# NEW_oct_6.net
KiCad netlist of a schematic drawn in EAGLE
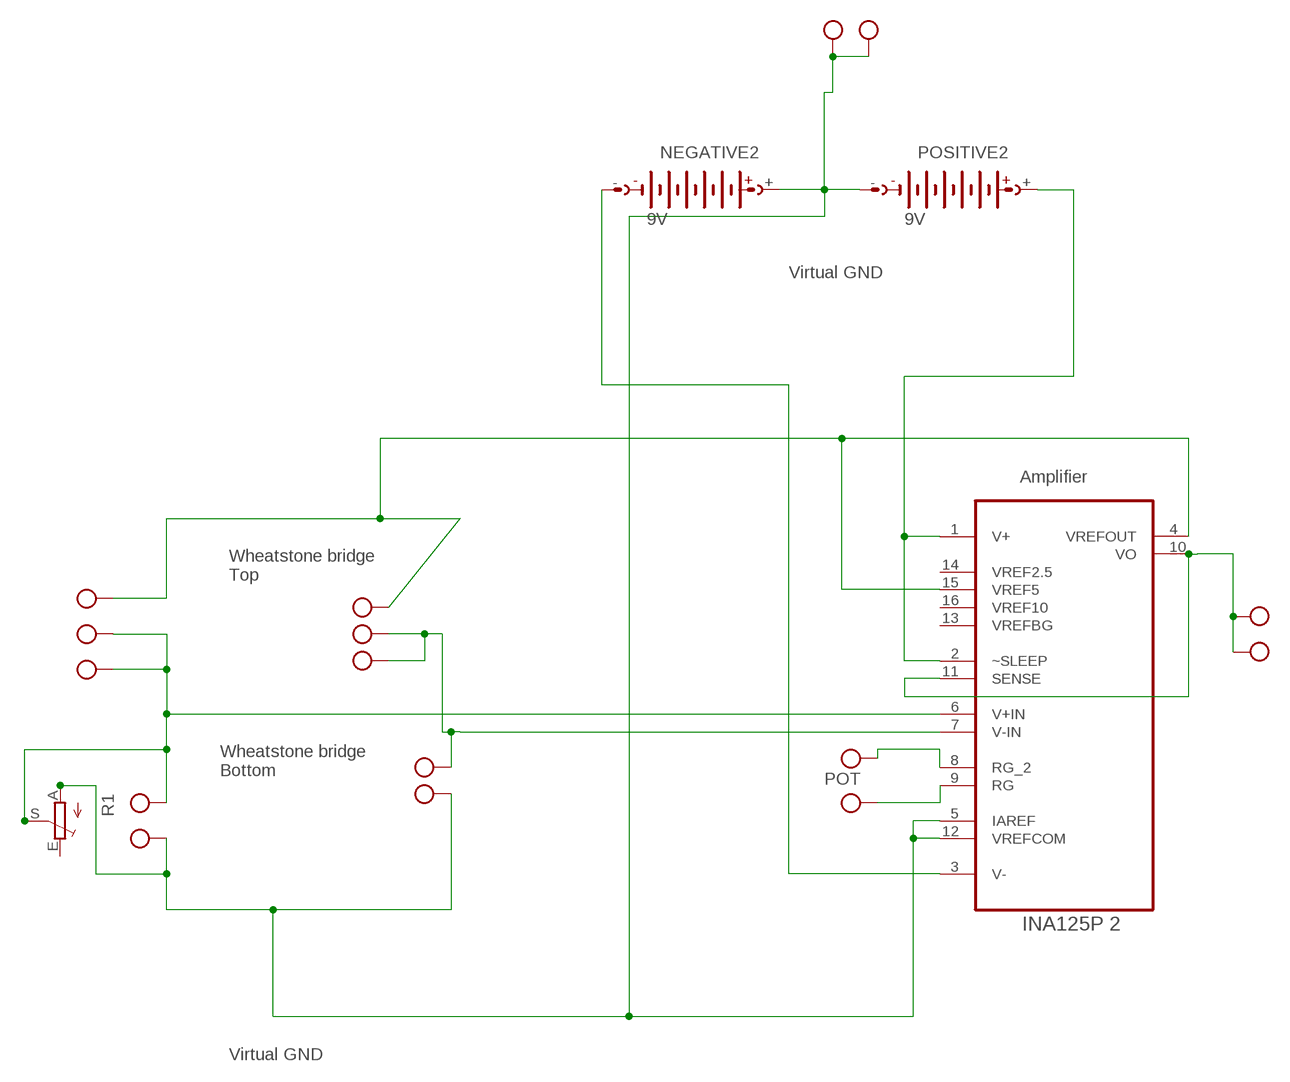
[diagram p0: schematic, sheet 1]

(export (version "E")
  (design (tool "Eeschema 10.0.6"))
  (components
    (comp (ref "FOURTH2")
      (value "W237-102")
      (footprint "eagle-import:W237-102")
      (fields (field (name "MPN") "237-102"))
      (libsource (lib "eagle-import") (part "W237-102"))
    )
    (comp (ref "FOURTH5")
      (value "W237-102")
      (footprint "eagle-import:W237-102")
      (fields (field (name "MPN") "237-102"))
      (libsource (lib "eagle-import") (part "W237-102"))
    )
    (comp (ref "FOURTH8")
      (value "W237-102")
      (footprint "eagle-import:W237-102")
      (fields (field (name "MPN") "237-102"))
      (libsource (lib "eagle-import") (part "W237-102"))
    )
    (comp (ref "NEGATIVE2")
      (value "AB9V")
      (footprint "eagle-import:AB9V")
      (libsource (lib "eagle-import") (part "AB9V"))
    )
    (comp (ref "POSITIVE2")
      (value "AB9V")
      (footprint "eagle-import:AB9V")
      (libsource (lib "eagle-import") (part "AB9V"))
    )
    (comp (ref "POT2")
      (value "W237-102")
      (footprint "eagle-import:W237-102")
      (fields (field (name "MPN") "237-102"))
      (libsource (lib "eagle-import") (part "W237-102"))
    )
    (comp (ref "R1")
      (value "TRIM_EU-CT6")
      (footprint "eagle-import:CT6")
      (libsource (lib "eagle-import") (part "TRIM_EU-CT6"))
    )
    (comp (ref "SECOND2")
      (value "W237-102")
      (footprint "eagle-import:W237-102")
      (fields (field (name "MPN") "237-102"))
      (libsource (lib "eagle-import") (part "W237-102"))
    )
    (comp (ref "U3")
      (value "INA125P 2")
      (footprint "eagle-import:DIP254P762X508-16")
      (fields (field (name "MF") "Texas Instruments") (field (name "MP") "INA125P"))
      (libsource (lib "eagle-import") (part "INA125P"))
    )
    (comp (ref "X1")
      (value "W237-103")
      (footprint "eagle-import:W237-103")
      (fields (field (name "MPN") "237-103"))
      (libsource (lib "eagle-import") (part "W237-103"))
    )
    (comp (ref "X2")
      (value "W237-103")
      (footprint "eagle-import:W237-103")
      (fields (field (name "MPN") "237-103"))
      (libsource (lib "eagle-import") (part "W237-103"))
    )
  )
  (nets
    (net (code "1") (name "/VREF2.5") (class "Default")
      (node (ref "U3") (pin "14") (pinfunction "VREF2.5_14") (pintype "power_in"))
    )
    (net (code "2") (name "/VREF10") (class "Default")
      (node (ref "U3") (pin "16") (pinfunction "VREF10_16") (pintype "power_in"))
    )
    (net (code "3") (name "/VREFBG") (class "Default")
      (node (ref "U3") (pin "13") (pinfunction "VREFBG_13") (pintype "power_in"))
    )
    (net (code "4") (name "Net-(FOURTH2A-KL)") (class "Default")
      (node (ref "FOURTH2") (pin "1") (pinfunction "KL_1") (pintype "passive"))
      (node (ref "FOURTH8") (pin "1") (pinfunction "KL_1") (pintype "passive"))
      (node (ref "FOURTH8") (pin "2") (pinfunction "KL_2") (pintype "passive"))
      (node (ref "NEGATIVE2") (pin "+") (pinfunction "+_+") (pintype "passive"))
      (node (ref "POSITIVE2") (pin "-") (pinfunction "-_-") (pintype "passive"))
      (node (ref "R1") (pin "A") (pinfunction "A_A") (pintype "passive"))
      (node (ref "SECOND2") (pin "2") (pinfunction "KL_2") (pintype "passive"))
      (node (ref "U3") (pin "12") (pinfunction "VREFCOM_12") (pintype "passive"))
      (node (ref "U3") (pin "5") (pinfunction "IAREF_5") (pintype "passive"))
    )
    (net (code "5") (name "Net-(FOURTH2B-KL)") (class "Default")
      (node (ref "FOURTH2") (pin "2") (pinfunction "KL_2") (pintype "passive"))
      (node (ref "U3") (pin "7") (pinfunction "V-IN_7") (pintype "power_in"))
      (node (ref "X2") (pin "1") (pinfunction "KL_1") (pintype "passive"))
      (node (ref "X2") (pin "2") (pinfunction "KL_2") (pintype "passive"))
    )
    (net (code "6") (name "Net-(FOURTH5A-KL)") (class "Default")
      (node (ref "FOURTH5") (pin "1") (pinfunction "KL_1") (pintype "passive"))
      (node (ref "FOURTH5") (pin "2") (pinfunction "KL_2") (pintype "passive"))
      (node (ref "U3") (pin "10") (pinfunction "VO_10") (pintype "output"))
      (node (ref "U3") (pin "11") (pinfunction "SENSE_11") (pintype "input"))
    )
    (net (code "7") (name "Net-(POT2A-KL)") (class "Default")
      (node (ref "POT2") (pin "1") (pinfunction "KL_1") (pintype "passive"))
      (node (ref "U3") (pin "8") (pinfunction "RG_2_8") (pintype "passive"))
    )
    (net (code "8") (name "Net-(POT2B-KL)") (class "Default")
      (node (ref "POT2") (pin "2") (pinfunction "KL_2") (pintype "passive"))
      (node (ref "U3") (pin "9") (pinfunction "RG_9") (pintype "passive"))
    )
    (net (code "9") (name "Net-(SECOND2A-KL)") (class "Default")
      (node (ref "R1") (pin "S") (pinfunction "S_S") (pintype "passive"))
      (node (ref "SECOND2") (pin "1") (pinfunction "KL_1") (pintype "passive"))
      (node (ref "U3") (pin "6") (pinfunction "V+IN_6") (pintype "power_in"))
      (node (ref "X1") (pin "2") (pinfunction "KL_2") (pintype "passive"))
      (node (ref "X1") (pin "3") (pinfunction "KL_3") (pintype "passive"))
    )
    (net (code "10") (name "Net-(U3-V+)") (class "Default")
      (node (ref "POSITIVE2") (pin "+") (pinfunction "+_+") (pintype "passive"))
      (node (ref "U3") (pin "1") (pinfunction "V+_1") (pintype "power_in"))
      (node (ref "U3") (pin "2") (pinfunction "~{SLEEP}_2") (pintype "passive"))
    )
    (net (code "11") (name "Net-(U3-V-)") (class "Default")
      (node (ref "NEGATIVE2") (pin "-") (pinfunction "-_-") (pintype "passive"))
      (node (ref "U3") (pin "3") (pinfunction "V-_3") (pintype "power_in"))
    )
    (net (code "12") (name "Net-(U3-VREF5)") (class "Default")
      (node (ref "U3") (pin "15") (pinfunction "VREF5_15") (pintype "power_in"))
      (node (ref "U3") (pin "4") (pinfunction "VREFOUT_4") (pintype "output"))
      (node (ref "X1") (pin "1") (pinfunction "KL_1") (pintype "passive"))
      (node (ref "X2") (pin "3") (pinfunction "KL_3") (pintype "passive"))
    )
    (net (code "13") (name "unconnected-(R1-PadE)") (class "Default")
      (node (ref "R1") (pin "E") (pinfunction "E_E") (pintype "passive"))
    )
  )
)
